# Wandering_point.net
KiCad netlist of a schematic drawn in EAGLE
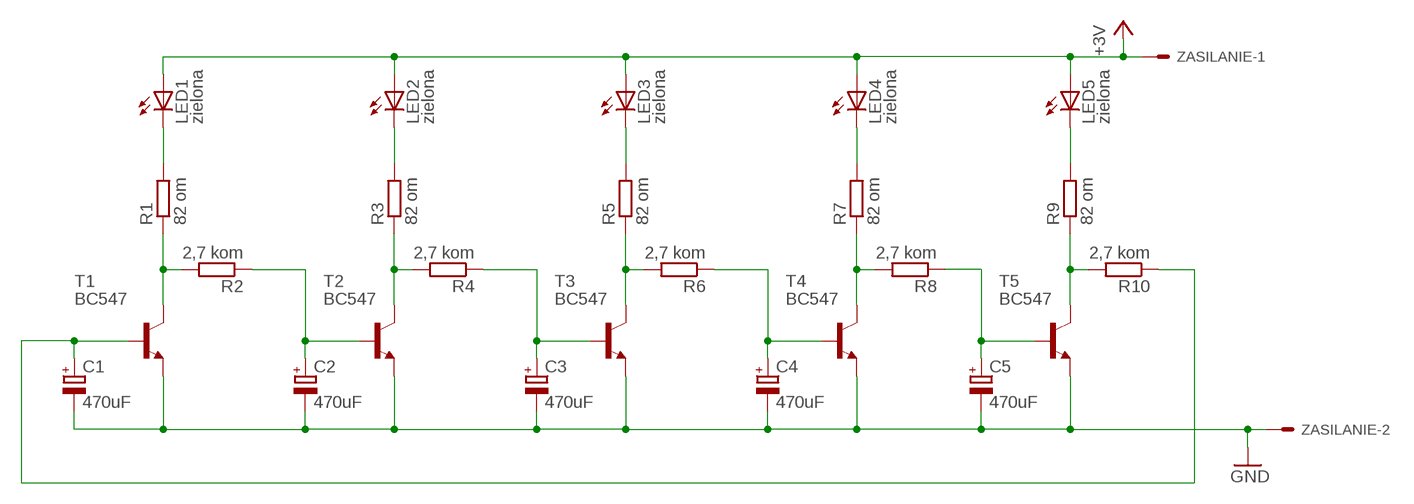
[diagram p0: schematic, sheet 1]

(export (version "E")
  (design (tool "Eeschema 10.0.6"))
  (components
    (comp (ref "C1")
      (value "470uF")
      (footprint "eagle-import:E7,5-16")
      (libsource (lib "eagle-import") (part "CPOL-EUE7.5-16"))
    )
    (comp (ref "C2")
      (value "470uF")
      (footprint "eagle-import:E7,5-16")
      (libsource (lib "eagle-import") (part "CPOL-EUE7.5-16"))
    )
    (comp (ref "C3")
      (value "470uF")
      (footprint "eagle-import:E7,5-16")
      (fields (field (name "SPICEPREFIX") "C"))
      (libsource (lib "eagle-import") (part "CPOL-EUE7.5-16"))
    )
    (comp (ref "C4")
      (value "470uF")
      (footprint "eagle-import:E7,5-16")
      (libsource (lib "eagle-import") (part "CPOL-EUE7.5-16"))
    )
    (comp (ref "C5")
      (value "470uF")
      (footprint "eagle-import:E7,5-16")
      (libsource (lib "eagle-import") (part "CPOL-EUE7.5-16"))
    )
    (comp (ref "LED1")
      (value "zielona")
      (footprint "eagle-import:LED5MM")
      (libsource (lib "eagle-import") (part "LED5MM"))
    )
    (comp (ref "LED2")
      (value "zielona")
      (footprint "eagle-import:LED5MM")
      (libsource (lib "eagle-import") (part "LED5MM"))
    )
    (comp (ref "LED3")
      (value "zielona")
      (footprint "eagle-import:LED5MM")
      (libsource (lib "eagle-import") (part "LED5MM"))
    )
    (comp (ref "LED4")
      (value "zielona")
      (footprint "eagle-import:LED5MM")
      (libsource (lib "eagle-import") (part "LED5MM"))
    )
    (comp (ref "LED5")
      (value "zielona")
      (footprint "eagle-import:LED5MM")
      (libsource (lib "eagle-import") (part "LED5MM"))
    )
    (comp (ref "R1")
      (value "82 om")
      (footprint "eagle-import:VMTA55")
      (libsource (lib "eagle-import") (part "R-EU_VMTA55"))
    )
    (comp (ref "R2")
      (value "2,7 kom")
      (footprint "eagle-import:VMTA55")
      (libsource (lib "eagle-import") (part "R-EU_VMTA55"))
    )
    (comp (ref "R3")
      (value "82 om")
      (footprint "eagle-import:VMTA55")
      (libsource (lib "eagle-import") (part "R-EU_VMTA55"))
    )
    (comp (ref "R4")
      (value "2,7 kom")
      (footprint "eagle-import:VMTA55")
      (libsource (lib "eagle-import") (part "R-EU_VMTA55"))
    )
    (comp (ref "R5")
      (value "82 om")
      (footprint "eagle-import:VMTA55")
      (libsource (lib "eagle-import") (part "R-EU_VMTA55"))
    )
    (comp (ref "R6")
      (value "2,7 kom")
      (footprint "eagle-import:VMTA55")
      (libsource (lib "eagle-import") (part "R-EU_VMTA55"))
    )
    (comp (ref "R7")
      (value "82 om")
      (footprint "eagle-import:VMTA55")
      (libsource (lib "eagle-import") (part "R-EU_VMTA55"))
    )
    (comp (ref "R8")
      (value "2,7 kom")
      (footprint "eagle-import:VMTA55")
      (libsource (lib "eagle-import") (part "R-EU_VMTA55"))
    )
    (comp (ref "R9")
      (value "82 om")
      (footprint "eagle-import:VMTA55")
      (libsource (lib "eagle-import") (part "R-EU_VMTA55"))
    )
    (comp (ref "R10")
      (value "2,7 kom")
      (footprint "eagle-import:VMTA55")
      (libsource (lib "eagle-import") (part "R-EU_VMTA55"))
    )
    (comp (ref "T1")
      (value "BC547")
      (footprint "eagle-import:TO92")
      (libsource (lib "eagle-import") (part "BC547"))
    )
    (comp (ref "T2")
      (value "BC547")
      (footprint "eagle-import:TO92")
      (libsource (lib "eagle-import") (part "BC547"))
    )
    (comp (ref "T3")
      (value "BC547")
      (footprint "eagle-import:TO92")
      (libsource (lib "eagle-import") (part "BC547"))
    )
    (comp (ref "T4")
      (value "BC547")
      (footprint "eagle-import:TO92")
      (libsource (lib "eagle-import") (part "BC547"))
    )
    (comp (ref "T5")
      (value "BC547")
      (footprint "eagle-import:TO92")
      (libsource (lib "eagle-import") (part "BC547"))
    )
    (comp (ref "ZASILANIE")
      (value "332-02")
      (footprint "eagle-import:332-02")
      (libsource (lib "eagle-import") (part "332-02"))
    )
  )
  (nets
    (net (code "1") (name "+3V") (class "Default")
      (node (ref "LED1") (pin "A") (pinfunction "A_A") (pintype "passive"))
      (node (ref "LED2") (pin "A") (pinfunction "A_A") (pintype "passive"))
      (node (ref "LED3") (pin "A") (pinfunction "A_A") (pintype "passive"))
      (node (ref "LED4") (pin "A") (pinfunction "A_A") (pintype "passive"))
      (node (ref "LED5") (pin "A") (pinfunction "A_A") (pintype "passive"))
      (node (ref "ZASILANIE") (pin "1") (pinfunction "S_1") (pintype "passive"))
    )
    (net (code "2") (name "GND") (class "Default")
      (node (ref "C1") (pin "-") (pinfunction "-_-") (pintype "passive"))
      (node (ref "C2") (pin "-") (pinfunction "-_-") (pintype "passive"))
      (node (ref "C3") (pin "-") (pinfunction "-_-") (pintype "passive"))
      (node (ref "C4") (pin "-") (pinfunction "-_-") (pintype "passive"))
      (node (ref "C5") (pin "-") (pinfunction "-_-") (pintype "passive"))
      (node (ref "T1") (pin "1") (pinfunction "E_1") (pintype "passive"))
      (node (ref "T2") (pin "1") (pinfunction "E_1") (pintype "passive"))
      (node (ref "T3") (pin "1") (pinfunction "E_1") (pintype "passive"))
      (node (ref "T4") (pin "1") (pinfunction "E_1") (pintype "passive"))
      (node (ref "T5") (pin "1") (pinfunction "E_1") (pintype "passive"))
      (node (ref "ZASILANIE") (pin "2") (pinfunction "S_2") (pintype "passive"))
    )
    (net (code "3") (name "Net-(LED1-C)") (class "Default")
      (node (ref "LED1") (pin "K") (pinfunction "C_K") (pintype "passive"))
      (node (ref "R1") (pin "2") (pinfunction "2_2") (pintype "passive"))
    )
    (net (code "4") (name "Net-(LED2-C)") (class "Default")
      (node (ref "LED2") (pin "K") (pinfunction "C_K") (pintype "passive"))
      (node (ref "R3") (pin "2") (pinfunction "2_2") (pintype "passive"))
    )
    (net (code "5") (name "Net-(LED3-C)") (class "Default")
      (node (ref "LED3") (pin "K") (pinfunction "C_K") (pintype "passive"))
      (node (ref "R5") (pin "2") (pinfunction "2_2") (pintype "passive"))
    )
    (net (code "6") (name "Net-(LED4-C)") (class "Default")
      (node (ref "LED4") (pin "K") (pinfunction "C_K") (pintype "passive"))
      (node (ref "R7") (pin "2") (pinfunction "2_2") (pintype "passive"))
    )
    (net (code "7") (name "Net-(LED5-C)") (class "Default")
      (node (ref "LED5") (pin "K") (pinfunction "C_K") (pintype "passive"))
      (node (ref "R9") (pin "2") (pinfunction "2_2") (pintype "passive"))
    )
    (net (code "8") (name "Net-(T1-B)") (class "Default")
      (node (ref "C1") (pin "+") (pinfunction "+_+") (pintype "passive"))
      (node (ref "R10") (pin "1") (pinfunction "1_1") (pintype "passive"))
      (node (ref "T1") (pin "2") (pinfunction "B_2") (pintype "passive"))
    )
    (net (code "9") (name "Net-(T1-C)") (class "Default")
      (node (ref "R1") (pin "1") (pinfunction "1_1") (pintype "passive"))
      (node (ref "R2") (pin "2") (pinfunction "2_2") (pintype "passive"))
      (node (ref "T1") (pin "3") (pinfunction "C_3") (pintype "passive"))
    )
    (net (code "10") (name "Net-(T2-B)") (class "Default")
      (node (ref "C2") (pin "+") (pinfunction "+_+") (pintype "passive"))
      (node (ref "R2") (pin "1") (pinfunction "1_1") (pintype "passive"))
      (node (ref "T2") (pin "2") (pinfunction "B_2") (pintype "passive"))
    )
    (net (code "11") (name "Net-(T2-C)") (class "Default")
      (node (ref "R3") (pin "1") (pinfunction "1_1") (pintype "passive"))
      (node (ref "R4") (pin "2") (pinfunction "2_2") (pintype "passive"))
      (node (ref "T2") (pin "3") (pinfunction "C_3") (pintype "passive"))
    )
    (net (code "12") (name "Net-(T3-B)") (class "Default")
      (node (ref "C3") (pin "+") (pinfunction "+_+") (pintype "passive"))
      (node (ref "R4") (pin "1") (pinfunction "1_1") (pintype "passive"))
      (node (ref "T3") (pin "2") (pinfunction "B_2") (pintype "passive"))
    )
    (net (code "13") (name "Net-(T3-C)") (class "Default")
      (node (ref "R5") (pin "1") (pinfunction "1_1") (pintype "passive"))
      (node (ref "R6") (pin "2") (pinfunction "2_2") (pintype "passive"))
      (node (ref "T3") (pin "3") (pinfunction "C_3") (pintype "passive"))
    )
    (net (code "14") (name "Net-(T4-B)") (class "Default")
      (node (ref "C4") (pin "+") (pinfunction "+_+") (pintype "passive"))
      (node (ref "R6") (pin "1") (pinfunction "1_1") (pintype "passive"))
      (node (ref "T4") (pin "2") (pinfunction "B_2") (pintype "passive"))
    )
    (net (code "15") (name "Net-(T4-C)") (class "Default")
      (node (ref "R7") (pin "1") (pinfunction "1_1") (pintype "passive"))
      (node (ref "R8") (pin "2") (pinfunction "2_2") (pintype "passive"))
      (node (ref "T4") (pin "3") (pinfunction "C_3") (pintype "passive"))
    )
    (net (code "16") (name "Net-(T5-B)") (class "Default")
      (node (ref "C5") (pin "+") (pinfunction "+_+") (pintype "passive"))
      (node (ref "R8") (pin "1") (pinfunction "1_1") (pintype "passive"))
      (node (ref "T5") (pin "2") (pinfunction "B_2") (pintype "passive"))
    )
    (net (code "17") (name "Net-(T5-C)") (class "Default")
      (node (ref "R10") (pin "2") (pinfunction "2_2") (pintype "passive"))
      (node (ref "R9") (pin "1") (pinfunction "1_1") (pintype "passive"))
      (node (ref "T5") (pin "3") (pinfunction "C_3") (pintype "passive"))
    )
  )
)
